# RaspberyConnector.net
KiCad netlist of a schematic drawn in Altium Designer
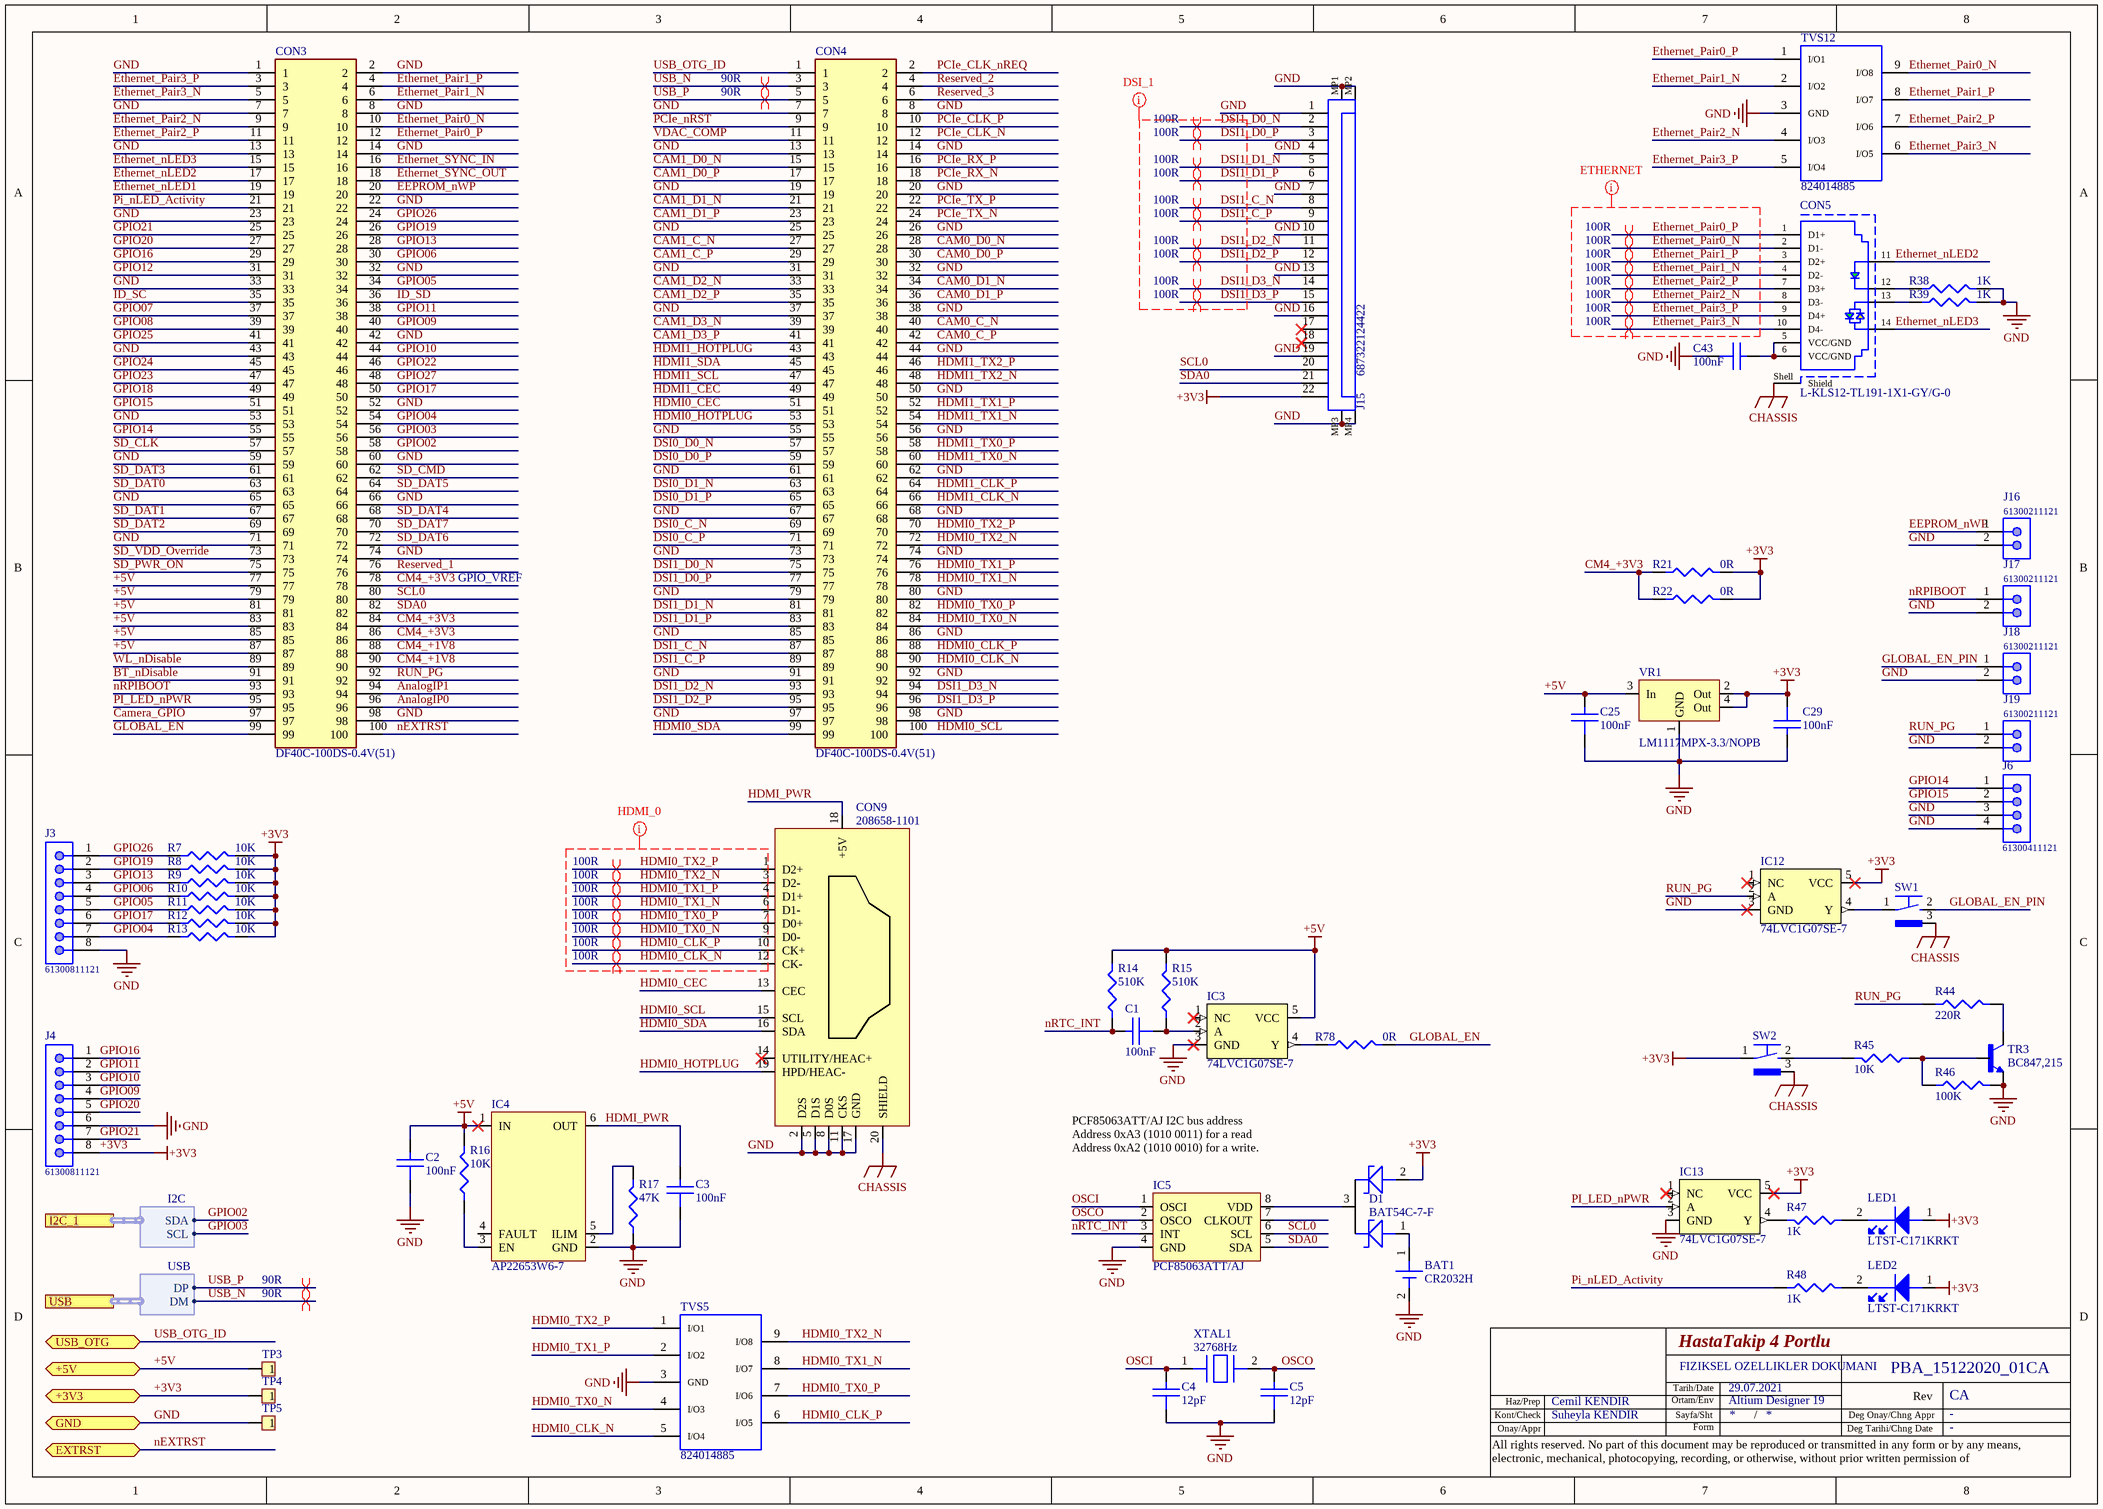
[diagram p0: RaspberyConnector.SchDoc]

(export (version "E")
  (design (tool "Eeschema 10.0.6"))
  (components
    (comp (ref "BAT1")
      (value "CR2032H")
      (footprint "CR2032H")
      (description "CR2032 Yatay Montaj")
      (libsource (lib "McmLibrary") (part "CR2032H"))
    )
    (comp (ref "C1")
      (value "100nF")
      (footprint "C0603")
      (description "100nF, 25V, X7R, 10%, 0603")
      (fields
        (field (name "MANUFACTURER") "Yageo")
        (field (name "MANUFACTURER PART NUMBER") "CC0603KRX7R8BB104")
      )
      (libsource (lib "McmLibrary") (part "CC0603KRX7R8BB104"))
    )
    (comp (ref "C2")
      (value "100nF")
      (footprint "C0603")
      (description "100nF, 25V, X7R, 10%, 0603")
      (fields
        (field (name "MANUFACTURER") "Yageo")
        (field (name "MANUFACTURER PART NUMBER") "CC0603KRX7R8BB104")
      )
      (libsource (lib "McmLibrary") (part "CC0603KRX7R8BB104"))
    )
    (comp (ref "C3")
      (value "100nF")
      (footprint "C0603")
      (description "100nF, 25V, X7R, 10%, 0603")
      (fields
        (field (name "MANUFACTURER") "Yageo")
        (field (name "MANUFACTURER PART NUMBER") "CC0603KRX7R8BB104")
      )
      (libsource (lib "McmLibrary") (part "CC0603KRX7R8BB104"))
    )
    (comp (ref "C4")
      (value "12pF")
      (footprint "C0603")
      (description "12pF 50V C0G 5% SMD 0603 125C T/R")
      (fields
        (field (name "MANUFACTURER") "Yageo")
        (field (name "MANUFACTURER PART NUMBER") "CC0603JRNPO9BN120")
      )
      (libsource (lib "McmLibrary") (part "CC0603JRNPO9BN120"))
    )
    (comp (ref "C5")
      (value "12pF")
      (footprint "C0603")
      (description "12pF 50V C0G 5% SMD 0603 125C T/R")
      (fields
        (field (name "MANUFACTURER") "Yageo")
        (field (name "MANUFACTURER PART NUMBER") "CC0603JRNPO9BN120")
      )
      (libsource (lib "McmLibrary") (part "CC0603JRNPO9BN120"))
    )
    (comp (ref "C25")
      (value "100nF")
      (footprint "C0603")
      (description "100nF, 25V, X7R, 10%, 0603")
      (fields
        (field (name "MANUFACTURER") "Yageo")
        (field (name "MANUFACTURER PART NUMBER") "CC0603KRX7R8BB104")
      )
      (libsource (lib "McmLibrary") (part "CC0603KRX7R8BB104"))
    )
    (comp (ref "C29")
      (value "100nF")
      (footprint "C0603")
      (description "100nF, 25V, X7R, 10%, 0603")
      (fields
        (field (name "MANUFACTURER") "Yageo")
        (field (name "MANUFACTURER PART NUMBER") "CC0603KRX7R8BB104")
      )
      (libsource (lib "McmLibrary") (part "CC0603KRX7R8BB104"))
    )
    (comp (ref "C43")
      (value "100nF")
      (footprint "C0603")
      (description "100nF, 25V, X7R, 10%, 0603")
      (fields
        (field (name "MANUFACTURER") "Yageo")
        (field (name "MANUFACTURER PART NUMBER") "CC0603KRX7R8BB104")
      )
      (libsource (lib "McmLibrary") (part "CC0603KRX7R8BB104"))
    )
    (comp (ref "CON3")
      (value "DF40C-100DS-0.4V(51)")
      (footprint "HRS_DF40C-100DS-0.4V(51)")
      (fields (field (name "MANUFACTURER") "Hirose"))
      (libsource (lib "McmLibrary") (part "DF40C-100DS-0.4V(51)"))
    )
    (comp (ref "CON4")
      (value "DF40C-100DS-0.4V(51)")
      (footprint "HRS_DF40C-100DS-0.4V(51)")
      (fields (field (name "MANUFACTURER") "Hirose"))
      (libsource (lib "McmLibrary") (part "DF40C-100DS-0.4V(51)"))
    )
    (comp (ref "CON5")
      (value "L-KLS12-TL191-1X1-GY/G-0")
      (footprint "L-KLS12-TL191-1X1-GY/G-0")
      (description "MODULAR JACK THT R/A 8P8C (RJ45,Ethernet) GRAY")
      (fields (field (name "MANUFACTURER") "KLS ELECTRONIC"))
      (libsource (lib "McmLibrary") (part "L-KLS12-TL191-1X1-GY/G-0"))
    )
    (comp (ref "CON9")
      (value "208658-1101")
      (footprint "2086581101")
      (description "HDMI; 0.5mm; v2.1; RT Angle; w/o Mylar; w/o Flange; 19 Circuits")
      (fields (field (name "MANUFACTURER") "Molex"))
      (libsource (lib "McmLibrary") (part "208658-1101"))
    )
    (comp (ref "D1")
      (value "BAT54C-7-F")
      (footprint "SOT23")
      (fields (field (name "MANUFACTURER") "Diodes"))
      (libsource (lib "McmLibrary") (part "BAT54C-7-F"))
    )
    (comp (ref "IC3")
      (value "74LVC1G07SE-7")
      (footprint "SOT353")
      (description "Buffer/Driver 1-CH Non-Inverting Open Drain CMOS 5-Pin SOT-353 T/R")
      (fields (field (name "MANUFACTURER") "Diodes"))
      (libsource (lib "InterfaceDriversReceiversTransceivers") (part "74LVC1G07SE-7"))
    )
    (comp (ref "IC4")
      (value "AP22653W6-7")
      (footprint "SOT23-6")
      (description "Power Switch/Driver 1:1 P-Channel 2.1A SOT-23-6")
      (fields (field (name "MANUFACTURER") "Diodes"))
      (libsource (lib "LoadDrivers") (part "AP22653W6-7"))
    )
    (comp (ref "IC5")
      (value "PCF85063ATT/AJ")
      (footprint "SOT505-1")
      (description "Real time clock, TSSOP-8,")
      (fields (field (name "MANUFACTURER") "NXP Semiconductors"))
      (libsource (lib "McmLibrary") (part "PCF85063ATT/AJ"))
    )
    (comp (ref "IC12")
      (value "74LVC1G07SE-7")
      (footprint "SOT353")
      (description "Buffer/Driver 1-CH Non-Inverting Open Drain CMOS 5-Pin SOT-353 T/R")
      (fields (field (name "MANUFACTURER") "Diodes"))
      (libsource (lib "InterfaceDriversReceiversTransceivers") (part "74LVC1G07SE-7"))
    )
    (comp (ref "IC13")
      (value "74LVC1G07SE-7")
      (footprint "SOT353")
      (description "Buffer/Driver 1-CH Non-Inverting Open Drain CMOS 5-Pin SOT-353 T/R")
      (fields (field (name "MANUFACTURER") "Diodes"))
      (libsource (lib "InterfaceDriversReceiversTransceivers") (part "74LVC1G07SE-7"))
    )
    (comp (ref "J3")
      (value "61300811121")
      (footprint "61300811121")
      (description "WR-PHD Pin Header, THT, pitch 2.54mm, Single Row, Vertical, 8pin")
      (fields (field (name "MANUFACTURER") "Wurth Electronics") (field (name "PUBLISHER") "Wurth Elektronik"))
      (libsource (lib "McmLibrary") (part "61300811121"))
    )
    (comp (ref "J4")
      (value "61300811121")
      (footprint "61300811121")
      (description "WR-PHD Pin Header, THT, pitch 2.54mm, Single Row, Vertical, 8pin")
      (fields (field (name "MANUFACTURER") "Wurth Electronics") (field (name "PUBLISHER") "Wurth Elektronik"))
      (libsource (lib "McmLibrary") (part "61300811121"))
    )
    (comp (ref "J6")
      (value "61300411121")
      (footprint "61300411121")
      (description "WR-PHD Pin Header, THT, pitch 2.54mm, Single Row, Vertical, 4pin")
      (fields (field (name "MANUFACTURER") "Wurth Electronics") (field (name "PUBLISHER") "Wurth Elektronik"))
      (libsource (lib "McmLibrary") (part "61300411121"))
    )
    (comp (ref "J15")
      (value "687322124422")
      (footprint "687322124422")
      (description "WR-FPC SMT ZIF Vertical, pitch 0.5mm, 22p")
      (fields (field (name "MANUFACTURER") "Wurth Elektronik") (field (name "PUBLISHER") "Wurth Elektronik"))
      (libsource (lib "Connectors") (part "687322124422"))
    )
    (comp (ref "J16")
      (value "61300211121")
      (footprint "61300211121")
      (description "WR-PHD Pin Header, THT, pitch 2.54mm, Single Row, Vertical, 2pin")
      (fields (field (name "MANUFACTURER") "Wurth Electronics") (field (name "PUBLISHER") "Wurth Elektronik"))
      (libsource (lib "McmLibrary") (part "61300211121"))
    )
    (comp (ref "J17")
      (value "61300211121")
      (footprint "61300211121")
      (description "WR-PHD Pin Header, THT, pitch 2.54mm, Single Row, Vertical, 2pin")
      (fields (field (name "MANUFACTURER") "Wurth Electronics") (field (name "PUBLISHER") "Wurth Elektronik"))
      (libsource (lib "McmLibrary") (part "61300211121"))
    )
    (comp (ref "J18")
      (value "61300211121")
      (footprint "61300211121")
      (description "WR-PHD Pin Header, THT, pitch 2.54mm, Single Row, Vertical, 2pin")
      (fields (field (name "MANUFACTURER") "Wurth Electronics") (field (name "PUBLISHER") "Wurth Elektronik"))
      (libsource (lib "McmLibrary") (part "61300211121"))
    )
    (comp (ref "J19")
      (value "61300211121")
      (footprint "61300211121")
      (description "WR-PHD Pin Header, THT, pitch 2.54mm, Single Row, Vertical, 2pin")
      (fields (field (name "MANUFACTURER") "Wurth Electronics") (field (name "PUBLISHER") "Wurth Elektronik"))
      (libsource (lib "McmLibrary") (part "61300211121"))
    )
    (comp (ref "LED1")
      (value "LTST-C171KRKT")
      (footprint "0805_RED")
      (description "LED RED CLEAR SMD")
      (fields (field (name "MANUFACTURER") "Vishay Lite-On"))
      (libsource (lib "McmLibrary") (part "LTST-C171KRKT"))
    )
    (comp (ref "LED2")
      (value "LTST-C171KRKT")
      (footprint "0805_RED")
      (description "LED RED CLEAR SMD")
      (fields (field (name "MANUFACTURER") "Vishay Lite-On"))
      (libsource (lib "McmLibrary") (part "LTST-C171KRKT"))
    )
    (comp (ref "R7")
      (value "10K")
      (footprint "R0603")
      (description "10K OHM 1% 1/10W 0603")
      (fields
        (field (name "MANUFACTURER") "Yageo")
        (field (name "MANUFACTURER PART NUMBER") "RT0603FRE0710KL")
      )
      (libsource (lib "McmLibrary") (part "RT0603FRE0710KL"))
    )
    (comp (ref "R8")
      (value "10K")
      (footprint "R0603")
      (description "10K OHM 1% 1/10W 0603")
      (fields
        (field (name "MANUFACTURER") "Yageo")
        (field (name "MANUFACTURER PART NUMBER") "RT0603FRE0710KL")
      )
      (libsource (lib "McmLibrary") (part "RT0603FRE0710KL"))
    )
    (comp (ref "R9")
      (value "10K")
      (footprint "R0603")
      (description "10K OHM 1% 1/10W 0603")
      (fields
        (field (name "MANUFACTURER") "Yageo")
        (field (name "MANUFACTURER PART NUMBER") "RT0603FRE0710KL")
      )
      (libsource (lib "McmLibrary") (part "RT0603FRE0710KL"))
    )
    (comp (ref "R10")
      (value "10K")
      (footprint "R0603")
      (description "10K OHM 1% 1/10W 0603")
      (fields
        (field (name "MANUFACTURER") "Yageo")
        (field (name "MANUFACTURER PART NUMBER") "RT0603FRE0710KL")
      )
      (libsource (lib "McmLibrary") (part "RT0603FRE0710KL"))
    )
    (comp (ref "R11")
      (value "10K")
      (footprint "R0603")
      (description "10K OHM 1% 1/10W 0603")
      (fields
        (field (name "MANUFACTURER") "Yageo")
        (field (name "MANUFACTURER PART NUMBER") "RT0603FRE0710KL")
      )
      (libsource (lib "McmLibrary") (part "RT0603FRE0710KL"))
    )
    (comp (ref "R12")
      (value "10K")
      (footprint "R0603")
      (description "10K OHM 1% 1/10W 0603")
      (fields
        (field (name "MANUFACTURER") "Yageo")
        (field (name "MANUFACTURER PART NUMBER") "RT0603FRE0710KL")
      )
      (libsource (lib "McmLibrary") (part "RT0603FRE0710KL"))
    )
    (comp (ref "R13")
      (value "10K")
      (footprint "R0603")
      (description "10K OHM 1% 1/10W 0603")
      (fields
        (field (name "MANUFACTURER") "Yageo")
        (field (name "MANUFACTURER PART NUMBER") "RT0603FRE0710KL")
      )
      (libsource (lib "McmLibrary") (part "RT0603FRE0710KL"))
    )
    (comp (ref "R14")
      (value "510K")
      (footprint "R0603")
      (description "510K, 1%, 1/10W, 0603")
      (fields
        (field (name "MANUFACTURER") "Yageo")
        (field (name "MANUFACTURER PART NUMBER") "RC0603FR-07510KL")
      )
      (libsource (lib "McmLibrary") (part "RC0603FR-07510KL"))
    )
    (comp (ref "R15")
      (value "510K")
      (footprint "R0603")
      (description "510K, 1%, 1/10W, 0603")
      (fields
        (field (name "MANUFACTURER") "Yageo")
        (field (name "MANUFACTURER PART NUMBER") "RC0603FR-07510KL")
      )
      (libsource (lib "McmLibrary") (part "RC0603FR-07510KL"))
    )
    (comp (ref "R16")
      (value "10K")
      (footprint "R0603")
      (description "10K OHM 1% 1/10W 0603")
      (fields
        (field (name "MANUFACTURER") "Yageo")
        (field (name "MANUFACTURER PART NUMBER") "RT0603FRE0710KL")
      )
      (libsource (lib "McmLibrary") (part "RT0603FRE0710KL"))
    )
    (comp (ref "R17")
      (value "47K")
      (footprint "R0603")
      (description "47K, 50V, 1/10W, 1%, 0603")
      (fields
        (field (name "MANUFACTURER") "Yageo")
        (field (name "MANUFACTURER PART NUMBER") "RC0603FR-0747KL")
      )
      (libsource (lib "McmLibrary") (part "RC0603FR-0747KL"))
    )
    (comp (ref "R21")
      (value "0R")
      (footprint "R0603")
      (description "0R ,%1 ,1/10 W ,0603")
      (fields
        (field (name "MANUFACTURER") "Yageo")
        (field (name "MANUFACTURER PART NUMBER") "RC0603FR-070RL")
      )
      (libsource (lib "McmLibrary") (part "RC0603FR-070RL"))
    )
    (comp (ref "R22")
      (value "0R")
      (footprint "R0603")
      (description "0R ,%1 ,1/10 W ,0603")
      (fields
        (field (name "MANUFACTURER") "Yageo")
        (field (name "MANUFACTURER PART NUMBER") "RC0603FR-070RL")
      )
      (libsource (lib "McmLibrary") (part "RC0603FR-070RL"))
    )
    (comp (ref "R38")
      (value "1K")
      (footprint "R0603")
      (description "1K ,%1 ,1/10 W ,0603")
      (fields
        (field (name "MANUFACTURER") "Yageo")
        (field (name "MANUFACTURER PART NUMBER") "RC0603FR-071KL")
      )
      (libsource (lib "McmLibrary") (part "RC0603FR-071KL"))
    )
    (comp (ref "R39")
      (value "1K")
      (footprint "R0603")
      (description "1K ,%1 ,1/10 W ,0603")
      (fields
        (field (name "MANUFACTURER") "Yageo")
        (field (name "MANUFACTURER PART NUMBER") "RC0603FR-071KL")
      )
      (libsource (lib "McmLibrary") (part "RC0603FR-071KL"))
    )
    (comp (ref "R44")
      (value "220R")
      (footprint "R0603")
      (description "220 R, %1, 1/10W, 0603")
      (fields
        (field (name "MANUFACTURER") "Yageo")
        (field (name "MANUFACTURER PART NUMBER") "RC0603FR-07220RL")
      )
      (libsource (lib "McmLibrary") (part "RC0603FR-07220RL"))
    )
    (comp (ref "R45")
      (value "10K")
      (footprint "R0603")
      (description "10K OHM 1% 1/10W 0603")
      (fields
        (field (name "MANUFACTURER") "Yageo")
        (field (name "MANUFACTURER PART NUMBER") "RT0603FRE0710KL")
      )
      (libsource (lib "McmLibrary") (part "RT0603FRE0710KL"))
    )
    (comp (ref "R46")
      (value "100K")
      (footprint "R0603")
      (description "100K ,%1 ,1/10 W ,0603")
      (fields
        (field (name "MANUFACTURER") "Yageo")
        (field (name "MANUFACTURER PART NUMBER") "RC0603FR-07100KL")
      )
      (libsource (lib "McmLibrary") (part "RC0603FR-07100KL"))
    )
    (comp (ref "R47")
      (value "1K")
      (footprint "R0603")
      (description "1K ,%1 ,1/10 W ,0603")
      (fields
        (field (name "MANUFACTURER") "Yageo")
        (field (name "MANUFACTURER PART NUMBER") "RC0603FR-071KL")
      )
      (libsource (lib "McmLibrary") (part "RC0603FR-071KL"))
    )
    (comp (ref "R48")
      (value "1K")
      (footprint "R0603")
      (description "1K ,%1 ,1/10 W ,0603")
      (fields
        (field (name "MANUFACTURER") "Yageo")
        (field (name "MANUFACTURER PART NUMBER") "RC0603FR-071KL")
      )
      (libsource (lib "McmLibrary") (part "RC0603FR-071KL"))
    )
    (comp (ref "R78")
      (value "0R")
      (footprint "R0603")
      (description "0R ,%1 ,1/10 W ,0603")
      (fields
        (field (name "MANUFACTURER") "Yageo")
        (field (name "MANUFACTURER PART NUMBER") "RC0603FR-070RL")
      )
      (libsource (lib "McmLibrary") (part "RC0603FR-070RL"))
    )
    (comp (ref "SW1")
      (value "FSMRACDAH")
      (footprint "FSMRACDAH")
      (description "Tactile Switches 6MM HGH TMP W/SQ ACT R/A TACT SWITCH")
      (fields (field (name "MANUFACTURER") "TE Connectivity"))
      (libsource (lib "McmLibrary") (part "FSMRACDAH"))
    )
    (comp (ref "SW2")
      (value "FSMRACDAH")
      (footprint "FSMRACDAH")
      (description "Tactile Switches 6MM HGH TMP W/SQ ACT R/A TACT SWITCH")
      (fields (field (name "MANUFACTURER") "TE Connectivity"))
      (libsource (lib "McmLibrary") (part "FSMRACDAH"))
    )
    (comp (ref "TP3")
      (value "TestPoint1")
      (footprint "SMD_2mmPoint")
      (description "test ölçüm noktası")
      (libsource (lib "McmLibrary") (part "TestPoint1"))
    )
    (comp (ref "TP4")
      (value "TestPoint1")
      (footprint "SMD_2mmPoint")
      (description "test ölçüm noktası")
      (libsource (lib "McmLibrary") (part "TestPoint1"))
    )
    (comp (ref "TP5")
      (value "TestPoint1")
      (footprint "SMD_2mmPoint")
      (description "test ölçüm noktası")
      (libsource (lib "McmLibrary") (part "TestPoint1"))
    )
    (comp (ref "TR3")
      (value "BC847,215")
      (footprint "SOT23")
      (description "TRANS NPN 45V 0.1A SOT23")
      (fields (field (name "MANUFACTURER") "Nexperia"))
      (libsource (lib "McmLibrary") (part "BC847,215"))
    )
    (comp (ref "TVS5")
      (value "824014885")
      (footprint "WE-TVS_DFN3810-9L")
      (description "TVS DIODE 5V 10.5V DFN3810-9")
      (fields (field (name "MANUFACTURER") "Wurth Electronics"))
      (libsource (lib "TVS") (part "824014885"))
    )
    (comp (ref "TVS12")
      (value "824014885")
      (footprint "WE-TVS_DFN3810-9L")
      (description "TVS DIODE 5V 10.5V DFN3810-9")
      (fields (field (name "MANUFACTURER") "Wurth Electronics"))
      (libsource (lib "TVS") (part "824014885"))
    )
    (comp (ref "VR1")
      (value "LM1117MPX-3.3/NOPB")
      (footprint "SOT223-3")
      (description "TEXAS INSTRUMENTS   LM1117MPX-3.3/NOPB.   LINEAR REG, FIX, 3.3V, 800MA, SOT-223-4, FULL REEL")
      (fields (field (name "MANUFACTURER") "Texas Instruments"))
      (libsource (lib "Regulator") (part "LM1117MPX-3.3/NOPB"))
    )
    (comp (ref "XTAL1")
      (value "32768Hz")
      (footprint "ForkCrystal")
      (description "CRYSTAL 32.7680KHZ 12.5PF T/H")
      (fields
        (field (name "MANUFACTURER") "Abracon")
        (field (name "MANUFACTURER PART NUMBER") "AB26T-32.768KHZ")
      )
      (libsource (lib "McmLibrary") (part "AB26T-32.768KHZ"))
    )
  )
  (nets
    (net (code "3") (name "+3V3") (class "Default")
      (node (ref "C29") (pin "2") (pintype "passive"))
      (node (ref "D1") (pin "2") (pinfunction "K_2") (pintype "passive"))
      (node (ref "IC12") (pin "5") (pinfunction "VCC_5") (pintype "power_in"))
      (node (ref "IC13") (pin "5") (pinfunction "VCC_5") (pintype "power_in"))
      (node (ref "J15") (pin "22") (pinfunction "22_22") (pintype "passive"))
      (node (ref "J4") (pin "8") (pinfunction "8_8") (pintype "passive"))
      (node (ref "LED1") (pin "1") (pinfunction "1_1") (pintype "passive"))
      (node (ref "LED2") (pin "1") (pinfunction "1_1") (pintype "passive"))
      (node (ref "R10") (pin "2") (pinfunction "2_2") (pintype "passive"))
      (node (ref "R11") (pin "2") (pinfunction "2_2") (pintype "passive"))
      (node (ref "R12") (pin "2") (pinfunction "2_2") (pintype "passive"))
      (node (ref "R13") (pin "2") (pinfunction "2_2") (pintype "passive"))
      (node (ref "R21") (pin "2") (pinfunction "2_2") (pintype "passive"))
      (node (ref "R22") (pin "2") (pinfunction "2_2") (pintype "passive"))
      (node (ref "R7") (pin "2") (pinfunction "2_2") (pintype "passive"))
      (node (ref "R8") (pin "2") (pinfunction "2_2") (pintype "passive"))
      (node (ref "R9") (pin "2") (pinfunction "2_2") (pintype "passive"))
      (node (ref "SW2") (pin "1") (pinfunction "1_1") (pintype "passive"))
      (node (ref "TP4") (pin "1") (pinfunction "1_1") (pintype "passive"))
      (node (ref "VR1") (pin "2") (pinfunction "Out_2") (pintype "passive"))
      (node (ref "VR1") (pin "4") (pinfunction "Out_4") (pintype "passive"))
    )
    (net (code "4") (name "+5V") (class "Default")
      (node (ref "C2") (pin "1") (pintype "passive"))
      (node (ref "C25") (pin "1") (pintype "passive"))
      (node (ref "CON3") (pin "77") (pinfunction "77_77") (pintype "passive"))
      (node (ref "CON3") (pin "79") (pinfunction "79_79") (pintype "passive"))
      (node (ref "CON3") (pin "81") (pinfunction "81_81") (pintype "passive"))
      (node (ref "CON3") (pin "83") (pinfunction "83_83") (pintype "passive"))
      (node (ref "CON3") (pin "85") (pinfunction "85_85") (pintype "passive"))
      (node (ref "CON3") (pin "87") (pinfunction "87_87") (pintype "passive"))
      (node (ref "IC3") (pin "5") (pinfunction "VCC_5") (pintype "power_in"))
      (node (ref "IC4") (pin "1") (pinfunction "IN_1") (pintype "passive"))
      (node (ref "R14") (pin "2") (pinfunction "2_2") (pintype "passive"))
      (node (ref "R15") (pin "2") (pinfunction "2_2") (pintype "passive"))
      (node (ref "R16") (pin "2") (pinfunction "2_2") (pintype "passive"))
      (node (ref "TP3") (pin "1") (pinfunction "1_1") (pintype "passive"))
      (node (ref "VR1") (pin "3") (pinfunction "In_3") (pintype "passive"))
    )
    (net (code "5") (name "/AnalogIP0") (class "Default")
      (node (ref "CON3") (pin "96") (pinfunction "96_96") (pintype "passive"))
    )
    (net (code "6") (name "/AnalogIP1") (class "Default")
      (node (ref "CON3") (pin "94") (pinfunction "94_94") (pintype "passive"))
    )
    (net (code "7") (name "/BT_nDisable") (class "Default")
      (node (ref "CON3") (pin "91") (pinfunction "91_91") (pintype "passive"))
    )
    (net (code "8") (name "/CAM0_C_N") (class "Default")
      (node (ref "CON4") (pin "40") (pinfunction "40_40") (pintype "passive"))
    )
    (net (code "9") (name "/CAM0_C_P") (class "Default")
      (node (ref "CON4") (pin "42") (pinfunction "42_42") (pintype "passive"))
    )
    (net (code "10") (name "/CAM0_D0_N") (class "Default")
      (node (ref "CON4") (pin "28") (pinfunction "28_28") (pintype "passive"))
    )
    (net (code "11") (name "/CAM0_D0_P") (class "Default")
      (node (ref "CON4") (pin "30") (pinfunction "30_30") (pintype "passive"))
    )
    (net (code "12") (name "/CAM0_D1_N") (class "Default")
      (node (ref "CON4") (pin "34") (pinfunction "34_34") (pintype "passive"))
    )
    (net (code "13") (name "/CAM0_D1_P") (class "Default")
      (node (ref "CON4") (pin "36") (pinfunction "36_36") (pintype "passive"))
    )
    (net (code "14") (name "/CAM1_C_N") (class "Default")
      (node (ref "CON4") (pin "27") (pinfunction "27_27") (pintype "passive"))
    )
    (net (code "15") (name "/CAM1_C_P") (class "Default")
      (node (ref "CON4") (pin "29") (pinfunction "29_29") (pintype "passive"))
    )
    (net (code "16") (name "/CAM1_D0_N") (class "Default")
      (node (ref "CON4") (pin "15") (pinfunction "15_15") (pintype "passive"))
    )
    (net (code "17") (name "/CAM1_D0_P") (class "Default")
      (node (ref "CON4") (pin "17") (pinfunction "17_17") (pintype "passive"))
    )
    (net (code "18") (name "/CAM1_D1_N") (class "Default")
      (node (ref "CON4") (pin "21") (pinfunction "21_21") (pintype "passive"))
    )
    (net (code "19") (name "/CAM1_D1_P") (class "Default")
      (node (ref "CON4") (pin "23") (pinfunction "23_23") (pintype "passive"))
    )
    (net (code "20") (name "/CAM1_D2_N") (class "Default")
      (node (ref "CON4") (pin "33") (pinfunction "33_33") (pintype "passive"))
    )
    (net (code "21") (name "/CAM1_D2_P") (class "Default")
      (node (ref "CON4") (pin "35") (pinfunction "35_35") (pintype "passive"))
    )
    (net (code "22") (name "/CAM1_D3_N") (class "Default")
      (node (ref "CON4") (pin "39") (pinfunction "39_39") (pintype "passive"))
    )
    (net (code "23") (name "/CAM1_D3_P") (class "Default")
      (node (ref "CON4") (pin "41") (pinfunction "41_41") (pintype "passive"))
    )
    (net (code "24") (name "/CM4_+1V8") (class "Default")
      (node (ref "CON3") (pin "88") (pinfunction "88_88") (pintype "passive"))
      (node (ref "CON3") (pin "90") (pinfunction "90_90") (pintype "passive"))
    )
    (net (code "25") (name "/CM4_+3V3") (class "Default")
      (node (ref "CON3") (pin "78") (pinfunction "78_78") (pintype "passive"))
      (node (ref "CON3") (pin "84") (pinfunction "84_84") (pintype "passive"))
      (node (ref "CON3") (pin "86") (pinfunction "86_86") (pintype "passive"))
      (node (ref "R21") (pin "1") (pinfunction "1_1") (pintype "passive"))
      (node (ref "R22") (pin "1") (pinfunction "1_1") (pintype "passive"))
    )
    (net (code "26") (name "/Camera_GPIO") (class "Default")
      (node (ref "CON3") (pin "97") (pinfunction "97_97") (pintype "passive"))
    )
    (net (code "27") (name "/DSI0_C_N") (class "Default")
      (node (ref "CON4") (pin "69") (pinfunction "69_69") (pintype "passive"))
    )
    (net (code "28") (name "/DSI0_C_P") (class "Default")
      (node (ref "CON4") (pin "71") (pinfunction "71_71") (pintype "passive"))
    )
    (net (code "29") (name "/DSI0_D0_N") (class "Default")
      (node (ref "CON4") (pin "57") (pinfunction "57_57") (pintype "passive"))
    )
    (net (code "30") (name "/DSI0_D0_P") (class "Default")
      (node (ref "CON4") (pin "59") (pinfunction "59_59") (pintype "passive"))
    )
    (net (code "31") (name "/DSI0_D1_N") (class "Default")
      (node (ref "CON4") (pin "63") (pinfunction "63_63") (pintype "passive"))
    )
    (net (code "32") (name "/DSI0_D1_P") (class "Default")
      (node (ref "CON4") (pin "65") (pinfunction "65_65") (pintype "passive"))
    )
    (net (code "33") (name "/DSI1_C_N") (class "Default")
      (node (ref "CON4") (pin "87") (pinfunction "87_87") (pintype "passive"))
      (node (ref "J15") (pin "8") (pinfunction "8_8") (pintype "passive"))
    )
    (net (code "34") (name "/DSI1_C_P") (class "Default")
      (node (ref "CON4") (pin "89") (pinfunction "89_89") (pintype "passive"))
      (node (ref "J15") (pin "9") (pinfunction "9_9") (pintype "passive"))
    )
    (net (code "35") (name "/DSI1_D0_N") (class "Default")
      (node (ref "CON4") (pin "75") (pinfunction "75_75") (pintype "passive"))
      (node (ref "J15") (pin "2") (pinfunction "2_2") (pintype "passive"))
    )
    (net (code "36") (name "/DSI1_D0_P") (class "Default")
      (node (ref "CON4") (pin "77") (pinfunction "77_77") (pintype "passive"))
      (node (ref "J15") (pin "3") (pinfunction "3_3") (pintype "passive"))
    )
    (net (code "37") (name "/DSI1_D1_N") (class "Default")
      (node (ref "CON4") (pin "81") (pinfunction "81_81") (pintype "passive"))
      (node (ref "J15") (pin "5") (pinfunction "5_5") (pintype "passive"))
    )
    (net (code "38") (name "/DSI1_D1_P") (class "Default")
      (node (ref "CON4") (pin "83") (pinfunction "83_83") (pintype "passive"))
      (node (ref "J15") (pin "6") (pinfunction "6_6") (pintype "passive"))
    )
    (net (code "39") (name "/DSI1_D2_N") (class "Default")
      (node (ref "CON4") (pin "93") (pinfunction "93_93") (pintype "passive"))
      (node (ref "J15") (pin "11") (pinfunction "11_11") (pintype "passive"))
    )
    (net (code "40") (name "/DSI1_D2_P") (class "Default")
      (node (ref "CON4") (pin "95") (pinfunction "95_95") (pintype "passive"))
      (node (ref "J15") (pin "12") (pinfunction "12_12") (pintype "passive"))
    )
    (net (code "41") (name "/DSI1_D3_N") (class "Default")
      (node (ref "CON4") (pin "94") (pinfunction "94_94") (pintype "passive"))
      (node (ref "J15") (pin "14") (pinfunction "14_14") (pintype "passive"))
    )
    (net (code "42") (name "/DSI1_D3_P") (class "Default")
      (node (ref "CON4") (pin "96") (pinfunction "96_96") (pintype "passive"))
      (node (ref "J15") (pin "15") (pinfunction "15_15") (pintype "passive"))
    )
    (net (code "43") (name "/EEPROM_nWP") (class "Default")
      (node (ref "CON3") (pin "20") (pinfunction "20_20") (pintype "passive"))
      (node (ref "J16") (pin "1") (pinfunction "1_1") (pintype "passive"))
    )
    (net (code "44") (name "/Ethernet_Pair0_N") (class "Default")
      (node (ref "CON3") (pin "10") (pinfunction "10_10") (pintype "passive"))
      (node (ref "CON5") (pin "2") (pinfunction "D1-_2") (pintype "passive"))
      (node (ref "TVS12") (pin "9") (pinfunction "I/O8_9") (pintype "passive"))
    )
    (net (code "45") (name "/Ethernet_Pair0_P") (class "Default")
      (node (ref "CON3") (pin "12") (pinfunction "12_12") (pintype "passive"))
      (node (ref "CON5") (pin "1") (pinfunction "D1+_1") (pintype "passive"))
      (node (ref "TVS12") (pin "1") (pinfunction "I/O1_1") (pintype "passive"))
    )
    (net (code "46") (name "/Ethernet_Pair1_N") (class "Default")
      (node (ref "CON3") (pin "6") (pinfunction "6_6") (pintype "passive"))
      (node (ref "CON5") (pin "4") (pinfunction "D2-_4") (pintype "passive"))
      (node (ref "TVS12") (pin "2") (pinfunction "I/O2_2") (pintype "passive"))
    )
    (net (code "47") (name "/Ethernet_Pair1_P") (class "Default")
      (node (ref "CON3") (pin "4") (pinfunction "4_4") (pintype "passive"))
      (node (ref "CON5") (pin "3") (pinfunction "D2+_3") (pintype "passive"))
      (node (ref "TVS12") (pin "8") (pinfunction "I/O7_8") (pintype "passive"))
    )
    (net (code "48") (name "/Ethernet_Pair2_N") (class "Default")
      (node (ref "CON3") (pin "9") (pinfunction "9_9") (pintype "passive"))
      (node (ref "CON5") (pin "8") (pinfunction "D3-_8") (pintype "passive"))
      (node (ref "TVS12") (pin "4") (pinfunction "I/O3_4") (pintype "passive"))
    )
    (net (code "49") (name "/Ethernet_Pair2_P") (class "Default")
      (node (ref "CON3") (pin "11") (pinfunction "11_11") (pintype "passive"))
      (node (ref "CON5") (pin "7") (pinfunction "D3+_7") (pintype "passive"))
      (node (ref "TVS12") (pin "7") (pinfunction "I/O6_7") (pintype "passive"))
    )
    (net (code "50") (name "/Ethernet_Pair3_N") (class "Default")
      (node (ref "CON3") (pin "5") (pinfunction "5_5") (pintype "passive"))
      (node (ref "CON5") (pin "10") (pinfunction "D4-_10") (pintype "passive"))
      (node (ref "TVS12") (pin "6") (pinfunction "I/O5_6") (pintype "passive"))
    )
    (net (code "51") (name "/Ethernet_Pair3_P") (class "Default")
      (node (ref "CON3") (pin "3") (pinfunction "3_3") (pintype "passive"))
      (node (ref "CON5") (pin "9") (pinfunction "D4+_9") (pintype "passive"))
      (node (ref "TVS12") (pin "5") (pinfunction "I/O4_5") (pintype "passive"))
    )
    (net (code "52") (name "/Ethernet_SYNC_IN") (class "Default")
      (node (ref "CON3") (pin "16") (pinfunction "16_16") (pintype "passive"))
    )
    (net (code "53") (name "/Ethernet_SYNC_OUT") (class "Default")
      (node (ref "CON3") (pin "18") (pinfunction "18_18") (pintype "passive"))
    )
    (net (code "54") (name "/Ethernet_nLED1") (class "Default")
      (node (ref "CON3") (pin "19") (pinfunction "19_19") (pintype "passive"))
    )
    (net (code "55") (name "/Ethernet_nLED2") (class "Default")
      (node (ref "CON3") (pin "17") (pinfunction "17_17") (pintype "passive"))
      (node (ref "CON5") (pin "11") (pinfunction "11_11") (pintype "passive"))
    )
    (net (code "56") (name "/Ethernet_nLED3") (class "Default")
      (node (ref "CON3") (pin "15") (pinfunction "15_15") (pintype "passive"))
      (node (ref "CON5") (pin "14") (pinfunction "14_14") (pintype "passive"))
    )
    (net (code "57") (name "/GLOBAL_EN") (class "Default")
      (node (ref "CON3") (pin "99") (pinfunction "99_99") (pintype "passive"))
      (node (ref "R78") (pin "2") (pinfunction "2_2") (pintype "passive"))
    )
    (net (code "58") (name "/GLOBAL_EN_PIN") (class "Default")
      (node (ref "J18") (pin "1") (pinfunction "1_1") (pintype "passive"))
      (node (ref "SW1") (pin "2") (pinfunction "2_2") (pintype "passive"))
    )
    (net (code "59") (name "/GPIO02") (class "Default")
      (node (ref "CON3") (pin "58") (pinfunction "58_58") (pintype "passive"))
    )
    (net (code "60") (name "/GPIO03") (class "Default")
      (node (ref "CON3") (pin "56") (pinfunction "56_56") (pintype "passive"))
    )
    (net (code "61") (name "/GPIO04") (class "Default")
      (node (ref "CON3") (pin "54") (pinfunction "54_54") (pintype "passive"))
      (node (ref "J3") (pin "7") (pinfunction "7_7") (pintype "passive"))
      (node (ref "R13") (pin "1") (pinfunction "1_1") (pintype "passive"))
    )
    (net (code "62") (name "/GPIO05") (class "Default")
      (node (ref "CON3") (pin "34") (pinfunction "34_34") (pintype "passive"))
      (node (ref "J3") (pin "5") (pinfunction "5_5") (pintype "passive"))
      (node (ref "R11") (pin "1") (pinfunction "1_1") (pintype "passive"))
    )
    (net (code "63") (name "/GPIO06") (class "Default")
      (node (ref "CON3") (pin "30") (pinfunction "30_30") (pintype "passive"))
      (node (ref "J3") (pin "4") (pinfunction "4_4") (pintype "passive"))
      (node (ref "R10") (pin "1") (pinfunction "1_1") (pintype "passive"))
    )
    (net (code "64") (name "/GPIO07") (class "Default")
      (node (ref "CON3") (pin "37") (pinfunction "37_37") (pintype "passive"))
    )
    (net (code "65") (name "/GPIO08") (class "Default")
      (node (ref "CON3") (pin "39") (pinfunction "39_39") (pintype "passive"))
    )
    (net (code "66") (name "/GPIO09") (class "Default")
      (node (ref "CON3") (pin "40") (pinfunction "40_40") (pintype "passive"))
      (node (ref "J4") (pin "4") (pinfunction "4_4") (pintype "passive"))
    )
    (net (code "67") (name "/GPIO10") (class "Default")
      (node (ref "CON3") (pin "44") (pinfunction "44_44") (pintype "passive"))
      (node (ref "J4") (pin "3") (pinfunction "3_3") (pintype "passive"))
    )
    (net (code "68") (name "/GPIO11") (class "Default")
      (node (ref "CON3") (pin "38") (pinfunction "38_38") (pintype "passive"))
      (node (ref "J4") (pin "2") (pinfunction "2_2") (pintype "passive"))
    )
    (net (code "69") (name "/GPIO12") (class "Default")
      (node (ref "CON3") (pin "31") (pinfunction "31_31") (pintype "passive"))
    )
    (net (code "70") (name "/GPIO13") (class "Default")
      (node (ref "CON3") (pin "28") (pinfunction "28_28") (pintype "passive"))
      (node (ref "J3") (pin "3") (pinfunction "3_3") (pintype "passive"))
      (node (ref "R9") (pin "1") (pinfunction "1_1") (pintype "passive"))
    )
    (net (code "71") (name "/GPIO14") (class "Default")
      (node (ref "CON3") (pin "55") (pinfunction "55_55") (pintype "passive"))
      (node (ref "J6") (pin "1") (pinfunction "1_1") (pintype "passive"))
    )
    (net (code "72") (name "/GPIO15") (class "Default")
      (node (ref "CON3") (pin "51") (pinfunction "51_51") (pintype "passive"))
      (node (ref "J6") (pin "2") (pinfunction "2_2") (pintype "passive"))
    )
    (net (code "73") (name "/GPIO16") (class "Default")
      (node (ref "CON3") (pin "29") (pinfunction "29_29") (pintype "passive"))
      (node (ref "J4") (pin "1") (pinfunction "1_1") (pintype "passive"))
    )
    (net (code "74") (name "/GPIO17") (class "Default")
      (node (ref "CON3") (pin "50") (pinfunction "50_50") (pintype "passive"))
      (node (ref "J3") (pin "6") (pinfunction "6_6") (pintype "passive"))
      (node (ref "R12") (pin "1") (pinfunction "1_1") (pintype "passive"))
    )
    (net (code "75") (name "/GPIO18") (class "Default")
      (node (ref "CON3") (pin "49") (pinfunction "49_49") (pintype "passive"))
    )
    (net (code "76") (name "/GPIO19") (class "Default")
      (node (ref "CON3") (pin "26") (pinfunction "26_26") (pintype "passive"))
      (node (ref "J3") (pin "2") (pinfunction "2_2") (pintype "passive"))
      (node (ref "R8") (pin "1") (pinfunction "1_1") (pintype "passive"))
    )
    (net (code "77") (name "/GPIO20") (class "Default")
      (node (ref "CON3") (pin "27") (pinfunction "27_27") (pintype "passive"))
      (node (ref "J4") (pin "5") (pinfunction "5_5") (pintype "passive"))
    )
    (net (code "78") (name "/GPIO21") (class "Default")
      (node (ref "CON3") (pin "25") (pinfunction "25_25") (pintype "passive"))
      (node (ref "J4") (pin "7") (pinfunction "7_7") (pintype "passive"))
    )
    (net (code "79") (name "/GPIO22") (class "Default")
      (node (ref "CON3") (pin "46") (pinfunction "46_46") (pintype "passive"))
    )
    (net (code "80") (name "/GPIO23") (class "Default")
      (node (ref "CON3") (pin "47") (pinfunction "47_47") (pintype "passive"))
    )
    (net (code "81") (name "/GPIO24") (class "Default")
      (node (ref "CON3") (pin "45") (pinfunction "45_45") (pintype "passive"))
    )
    (net (code "82") (name "/GPIO25") (class "Default")
      (node (ref "CON3") (pin "41") (pinfunction "41_41") (pintype "passive"))
    )
    (net (code "83") (name "/GPIO26") (class "Default")
      (node (ref "CON3") (pin "24") (pinfunction "24_24") (pintype "passive"))
      (node (ref "J3") (pin "1") (pinfunction "1_1") (pintype "passive"))
      (node (ref "R7") (pin "1") (pinfunction "1_1") (pintype "passive"))
    )
    (net (code "84") (name "/GPIO27") (class "Default")
      (node (ref "CON3") (pin "48") (pinfunction "48_48") (pintype "passive"))
    )
    (net (code "85") (name "/HDMI0_CEC") (class "Default")
      (node (ref "CON4") (pin "51") (pinfunction "51_51") (pintype "passive"))
      (node (ref "CON9") (pin "13") (pinfunction "CEC_13") (pintype "passive"))
    )
    (net (code "86") (name "/HDMI0_CLK_N") (class "Default")
      (node (ref "CON4") (pin "90") (pinfunction "90_90") (pintype "passive"))
      (node (ref "CON9") (pin "12") (pinfunction "CK-_12") (pintype "passive"))
      (node (ref "TVS5") (pin "5") (pinfunction "I/O4_5") (pintype "passive"))
    )
    (net (code "87") (name "/HDMI0_CLK_P") (class "Default")
      (node (ref "CON4") (pin "88") (pinfunction "88_88") (pintype "passive"))
      (node (ref "CON9") (pin "10") (pinfunction "CK+_10") (pintype "passive"))
      (node (ref "TVS5") (pin "6") (pinfunction "I/O5_6") (pintype "passive"))
    )
    (net (code "88") (name "/HDMI0_HOTPLUG") (class "Default")
      (node (ref "CON4") (pin "53") (pinfunction "53_53") (pintype "passive"))
      (node (ref "CON9") (pin "19") (pinfunction "HPD/HEAC-_19") (pintype "passive"))
    )
    (net (code "89") (name "/HDMI0_SCL") (class "Default")
      (node (ref "CON4") (pin "100") (pinfunction "100_100") (pintype "passive"))
      (node (ref "CON9") (pin "15") (pinfunction "SCL_15") (pintype "passive"))
    )
    (net (code "90") (name "/HDMI0_SDA") (class "Default")
      (node (ref "CON4") (pin "99") (pinfunction "99_99") (pintype "passive"))
      (node (ref "CON9") (pin "16") (pinfunction "SDA_16") (pintype "passive"))
    )
    (net (code "91") (name "/HDMI0_TX0_N") (class "Default")
      (node (ref "CON4") (pin "84") (pinfunction "84_84") (pintype "passive"))
      (node (ref "CON9") (pin "9") (pinfunction "D0-_9") (pintype "passive"))
      (node (ref "TVS5") (pin "4") (pinfunction "I/O3_4") (pintype "passive"))
    )
    (net (code "92") (name "/HDMI0_TX0_P") (class "Default")
      (node (ref "CON4") (pin "82") (pinfunction "82_82") (pintype "passive"))
      (node (ref "CON9") (pin "7") (pinfunction "D0+_7") (pintype "passive"))
      (node (ref "TVS5") (pin "7") (pinfunction "I/O6_7") (pintype "passive"))
    )
    (net (code "93") (name "/HDMI0_TX1_N") (class "Default")
      (node (ref "CON4") (pin "78") (pinfunction "78_78") (pintype "passive"))
      (node (ref "CON9") (pin "6") (pinfunction "D1-_6") (pintype "passive"))
      (node (ref "TVS5") (pin "8") (pinfunction "I/O7_8") (pintype "passive"))
    )
    (net (code "94") (name "/HDMI0_TX1_P") (class "Default")
      (node (ref "CON4") (pin "76") (pinfunction "76_76") (pintype "passive"))
      (node (ref "CON9") (pin "4") (pinfunction "D1+_4") (pintype "passive"))
      (node (ref "TVS5") (pin "2") (pinfunction "I/O2_2") (pintype "passive"))
    )
    (net (code "95") (name "/HDMI0_TX2_N") (class "Default")
      (node (ref "CON4") (pin "72") (pinfunction "72_72") (pintype "passive"))
      (node (ref "CON9") (pin "3") (pinfunction "D2-_3") (pintype "passive"))
      (node (ref "TVS5") (pin "9") (pinfunction "I/O8_9") (pintype "passive"))
    )
    (net (code "96") (name "/HDMI0_TX2_P") (class "Default")
      (node (ref "CON4") (pin "70") (pinfunction "70_70") (pintype "passive"))
      (node (ref "CON9") (pin "1") (pinfunction "D2+_1") (pintype "passive"))
      (node (ref "TVS5") (pin "1") (pinfunction "I/O1_1") (pintype "passive"))
    )
    (net (code "97") (name "/HDMI1_CEC") (class "Default")
      (node (ref "CON4") (pin "49") (pinfunction "49_49") (pintype "passive"))
    )
    (net (code "98") (name "/HDMI1_CLK_N") (class "Default")
      (node (ref "CON4") (pin "66") (pinfunction "66_66") (pintype "passive"))
    )
    (net (code "99") (name "/HDMI1_CLK_P") (class "Default")
      (node (ref "CON4") (pin "64") (pinfunction "64_64") (pintype "passive"))
    )
    (net (code "100") (name "/HDMI1_HOTPLUG") (class "Default")
      (node (ref "CON4") (pin "43") (pinfunction "43_43") (pintype "passive"))
    )
    (net (code "101") (name "/HDMI1_SCL") (class "Default")
      (node (ref "CON4") (pin "47") (pinfunction "47_47") (pintype "passive"))
    )
    (net (code "102") (name "/HDMI1_SDA") (class "Default")
      (node (ref "CON4") (pin "45") (pinfunction "45_45") (pintype "passive"))
    )
    (net (code "103") (name "/HDMI1_TX0_N") (class "Default")
      (node (ref "CON4") (pin "60") (pinfunction "60_60") (pintype "passive"))
    )
    (net (code "104") (name "/HDMI1_TX0_P") (class "Default")
      (node (ref "CON4") (pin "58") (pinfunction "58_58") (pintype "passive"))
    )
    (net (code "105") (name "/HDMI1_TX1_N") (class "Default")
      (node (ref "CON4") (pin "54") (pinfunction "54_54") (pintype "passive"))
    )
    (net (code "106") (name "/HDMI1_TX1_P") (class "Default")
      (node (ref "CON4") (pin "52") (pinfunction "52_52") (pintype "passive"))
    )
    (net (code "107") (name "/HDMI1_TX2_N") (class "Default")
      (node (ref "CON4") (pin "48") (pinfunction "48_48") (pintype "passive"))
    )
    (net (code "108") (name "/HDMI1_TX2_P") (class "Default")
      (node (ref "CON4") (pin "46") (pinfunction "46_46") (pintype "passive"))
    )
    (net (code "109") (name "/HDMI_PWR") (class "Default")
      (node (ref "C3") (pin "1") (pintype "passive"))
      (node (ref "CON9") (pin "18") (pinfunction "+5V_18") (pintype "passive"))
      (node (ref "IC4") (pin "6") (pinfunction "OUT_6") (pintype "passive"))
    )
    (net (code "110") (name "/ID_SC") (class "Default")
      (node (ref "CON3") (pin "35") (pinfunction "35_35") (pintype "passive"))
    )
    (net (code "111") (name "/ID_SD") (class "Default")
      (node (ref "CON3") (pin "36") (pinfunction "36_36") (pintype "passive"))
    )
    (net (code "112") (name "/OSCI") (class "Default")
      (node (ref "C4") (pin "1") (pintype "passive"))
      (node (ref "IC5") (pin "1") (pinfunction "OSCI_1") (pintype "passive"))
      (node (ref "XTAL1") (pin "1") (pinfunction "1_1") (pintype "passive"))
    )
    (net (code "113") (name "/OSCO") (class "Default")
      (node (ref "C5") (pin "1") (pintype "passive"))
      (node (ref "IC5") (pin "2") (pinfunction "OSCO_2") (pintype "passive"))
      (node (ref "XTAL1") (pin "2") (pinfunction "2_2") (pintype "passive"))
    )
    (net (code "114") (name "/PCIe_CLK_N") (class "Default")
      (node (ref "CON4") (pin "12") (pinfunction "12_12") (pintype "passive"))
    )
    (net (code "115") (name "/PCIe_CLK_P") (class "Default")
      (node (ref "CON4") (pin "10") (pinfunction "10_10") (pintype "passive"))
    )
    (net (code "116") (name "/PCIe_CLK_nREQ") (class "Default")
      (node (ref "CON4") (pin "2") (pinfunction "2_2") (pintype "passive"))
    )
    (net (code "117") (name "/PCIe_RX_N") (class "Default")
      (node (ref "CON4") (pin "18") (pinfunction "18_18") (pintype "passive"))
    )
    (net (code "118") (name "/PCIe_RX_P") (class "Default")
      (node (ref "CON4") (pin "16") (pinfunction "16_16") (pintype "passive"))
    )
    (net (code "119") (name "/PCIe_TX_N") (class "Default")
      (node (ref "CON4") (pin "24") (pinfunction "24_24") (pintype "passive"))
    )
    (net (code "120") (name "/PCIe_TX_P") (class "Default")
      (node (ref "CON4") (pin "22") (pinfunction "22_22") (pintype "passive"))
    )
    (net (code "121") (name "/PCIe_nRST") (class "Default")
      (node (ref "CON4") (pin "9") (pinfunction "9_9") (pintype "passive"))
    )
    (net (code "122") (name "/PI_LED_nPWR") (class "Default")
      (node (ref "CON3") (pin "95") (pinfunction "95_95") (pintype "passive"))
      (node (ref "IC13") (pin "2") (pinfunction "A_2") (pintype "input"))
    )
    (net (code "123") (name "/Pi_nLED_Activity") (class "Default")
      (node (ref "CON3") (pin "21") (pinfunction "21_21") (pintype "passive"))
      (node (ref "R48") (pin "1") (pinfunction "1_1") (pintype "passive"))
    )
    (net (code "124") (name "/RUN_PG") (class "Default")
      (node (ref "CON3") (pin "92") (pinfunction "92_92") (pintype "passive"))
      (node (ref "IC12") (pin "2") (pinfunction "A_2") (pintype "input"))
      (node (ref "J19") (pin "1") (pinfunction "1_1") (pintype "passive"))
      (node (ref "R44") (pin "1") (pinfunction "1_1") (pintype "passive"))
    )
    (net (code "125") (name "/Reserved_1") (class "Default")
      (node (ref "CON3") (pin "76") (pinfunction "76_76") (pintype "passive"))
    )
    (net (code "126") (name "/Reserved_2") (class "Default")
      (node (ref "CON4") (pin "4") (pinfunction "4_4") (pintype "passive"))
    )
    (net (code "127") (name "/Reserved_3") (class "Default")
      (node (ref "CON4") (pin "6") (pinfunction "6_6") (pintype "passive"))
    )
    (net (code "128") (name "/SCL0") (class "Default")
      (node (ref "CON3") (pin "80") (pinfunction "80_80") (pintype "passive"))
      (node (ref "IC5") (pin "6") (pinfunction "SCL_6") (pintype "passive"))
      (node (ref "J15") (pin "20") (pinfunction "20_20") (pintype "passive"))
    )
    (net (code "129") (name "/SDA0") (class "Default")
      (node (ref "CON3") (pin "82") (pinfunction "82_82") (pintype "passive"))
      (node (ref "IC5") (pin "5") (pinfunction "SDA_5") (pintype "passive"))
      (node (ref "J15") (pin "21") (pinfunction "21_21") (pintype "passive"))
    )
    (net (code "130") (name "/SD_CLK") (class "Default")
      (node (ref "CON3") (pin "57") (pinfunction "57_57") (pintype "passive"))
    )
    (net (code "131") (name "/SD_CMD") (class "Default")
      (node (ref "CON3") (pin "62") (pinfunction "62_62") (pintype "passive"))
    )
    (net (code "132") (name "/SD_DAT0") (class "Default")
      (node (ref "CON3") (pin "63") (pinfunction "63_63") (pintype "passive"))
    )
    (net (code "133") (name "/SD_DAT1") (class "Default")
      (node (ref "CON3") (pin "67") (pinfunction "67_67") (pintype "passive"))
    )
    (net (code "134") (name "/SD_DAT2") (class "Default")
      (node (ref "CON3") (pin "69") (pinfunction "69_69") (pintype "passive"))
    )
    (net (code "135") (name "/SD_DAT3") (class "Default")
      (node (ref "CON3") (pin "61") (pinfunction "61_61") (pintype "passive"))
    )
    (net (code "136") (name "/SD_DAT4") (class "Default")
      (node (ref "CON3") (pin "68") (pinfunction "68_68") (pintype "passive"))
    )
    (net (code "137") (name "/SD_DAT5") (class "Default")
      (node (ref "CON3") (pin "64") (pinfunction "64_64") (pintype "passive"))
    )
    (net (code "138") (name "/SD_DAT6") (class "Default")
      (node (ref "CON3") (pin "72") (pinfunction "72_72") (pintype "passive"))
    )
    (net (code "139") (name "/SD_DAT7") (class "Default")
      (node (ref "CON3") (pin "70") (pinfunction "70_70") (pintype "passive"))
    )
    (net (code "140") (name "/SD_PWR_ON") (class "Default")
      (node (ref "CON3") (pin "75") (pinfunction "75_75") (pintype "passive"))
    )
    (net (code "141") (name "/SD_VDD_Override") (class "Default")
      (node (ref "CON3") (pin "73") (pinfunction "73_73") (pintype "passive"))
    )
    (net (code "142") (name "/USB_N") (class "Default")
      (node (ref "CON4") (pin "3") (pinfunction "3_3") (pintype "passive"))
    )
    (net (code "143") (name "/USB_OTG_ID") (class "Default")
      (node (ref "CON4") (pin "1") (pinfunction "1_1") (pintype "passive"))
    )
    (net (code "144") (name "/USB_P") (class "Default")
      (node (ref "CON4") (pin "5") (pinfunction "5_5") (pintype "passive"))
    )
    (net (code "145") (name "/VDAC_COMP") (class "Default")
      (node (ref "CON4") (pin "11") (pinfunction "11_11") (pintype "passive"))
    )
    (net (code "146") (name "/WL_nDisable") (class "Default")
      (node (ref "CON3") (pin "89") (pinfunction "89_89") (pintype "passive"))
    )
    (net (code "147") (name "/nEXTRST") (class "Default")
      (node (ref "CON3") (pin "100") (pinfunction "100_100") (pintype "passive"))
    )
    (net (code "148") (name "/nRPIBOOT") (class "Default")
      (node (ref "CON3") (pin "93") (pinfunction "93_93") (pintype "passive"))
      (node (ref "J17") (pin "1") (pinfunction "1_1") (pintype "passive"))
    )
    (net (code "149") (name "/nRTC_INT") (class "Default")
      (node (ref "C1") (pin "1") (pintype "passive"))
      (node (ref "IC5") (pin "3") (pinfunction "INT_3") (pintype "passive"))
      (node (ref "R14") (pin "1") (pinfunction "1_1") (pintype "passive"))
    )
    (net (code "152") (name "CHASSIS") (class "Default")
      (node (ref "CON5") (pin "Shell") (pinfunction "Shield_Shell") (pintype "passive"))
      (node (ref "CON9") (pin "20") (pinfunction "SHIELD_20") (pintype "passive"))
      (node (ref "SW1") (pin "3") (pinfunction "3_3") (pintype "passive"))
      (node (ref "SW2") (pin "3") (pinfunction "3_3") (pintype "passive"))
    )
    (net (code "153") (name "GND") (class "Default")
      (node (ref "BAT1") (pin "2") (pinfunction "2_2") (pintype "passive"))
      (node (ref "C2") (pin "2") (pintype "passive"))
      (node (ref "C25") (pin "2") (pintype "passive"))
      (node (ref "C29") (pin "1") (pintype "passive"))
      (node (ref "C3") (pin "2") (pintype "passive"))
      (node (ref "C4") (pin "2") (pintype "passive"))
      (node (ref "C43") (pin "2") (pintype "passive"))
      (node (ref "C5") (pin "2") (pintype "passive"))
      (node (ref "CON3") (pin "1") (pinfunction "1_1") (pintype "passive"))
      (node (ref "CON3") (pin "13") (pinfunction "13_13") (pintype "passive"))
      (node (ref "CON3") (pin "14") (pinfunction "14_14") (pintype "passive"))
      (node (ref "CON3") (pin "2") (pinfunction "2_2") (pintype "passive"))
      (node (ref "CON3") (pin "22") (pinfunction "22_22") (pintype "passive"))
      (node (ref "CON3") (pin "23") (pinfunction "23_23") (pintype "passive"))
      (node (ref "CON3") (pin "32") (pinfunction "32_32") (pintype "passive"))
      (node (ref "CON3") (pin "33") (pinfunction "33_33") (pintype "passive"))
      (node (ref "CON3") (pin "42") (pinfunction "42_42") (pintype "passive"))
      (node (ref "CON3") (pin "43") (pinfunction "43_43") (pintype "passive"))
      (node (ref "CON3") (pin "52") (pinfunction "52_52") (pintype "passive"))
      (node (ref "CON3") (pin "53") (pinfunction "53_53") (pintype "passive"))
      (node (ref "CON3") (pin "59") (pinfunction "59_59") (pintype "passive"))
      (node (ref "CON3") (pin "60") (pinfunction "60_60") (pintype "passive"))
      (node (ref "CON3") (pin "65") (pinfunction "65_65") (pintype "passive"))
      (node (ref "CON3") (pin "66") (pinfunction "66_66") (pintype "passive"))
      (node (ref "CON3") (pin "7") (pinfunction "7_7") (pintype "passive"))
      (node (ref "CON3") (pin "71") (pinfunction "71_71") (pintype "passive"))
      (node (ref "CON3") (pin "74") (pinfunction "74_74") (pintype "passive"))
      (node (ref "CON3") (pin "8") (pinfunction "8_8") (pintype "passive"))
      (node (ref "CON3") (pin "98") (pinfunction "98_98") (pintype "passive"))
      (node (ref "CON4") (pin "13") (pinfunction "13_13") (pintype "passive"))
      (node (ref "CON4") (pin "14") (pinfunction "14_14") (pintype "passive"))
      (node (ref "CON4") (pin "19") (pinfunction "19_19") (pintype "passive"))
      (node (ref "CON4") (pin "20") (pinfunction "20_20") (pintype "passive"))
      (node (ref "CON4") (pin "25") (pinfunction "25_25") (pintype "passive"))
      (node (ref "CON4") (pin "26") (pinfunction "26_26") (pintype "passive"))
      (node (ref "CON4") (pin "31") (pinfunction "31_31") (pintype "passive"))
      (node (ref "CON4") (pin "32") (pinfunction "32_32") (pintype "passive"))
      (node (ref "CON4") (pin "37") (pinfunction "37_37") (pintype "passive"))
      (node (ref "CON4") (pin "38") (pinfunction "38_38") (pintype "passive"))
      (node (ref "CON4") (pin "44") (pinfunction "44_44") (pintype "passive"))
      (node (ref "CON4") (pin "50") (pinfunction "50_50") (pintype "passive"))
      (node (ref "CON4") (pin "55") (pinfunction "55_55") (pintype "passive"))
      (node (ref "CON4") (pin "56") (pinfunction "56_56") (pintype "passive"))
      (node (ref "CON4") (pin "61") (pinfunction "61_61") (pintype "passive"))
      (node (ref "CON4") (pin "62") (pinfunction "62_62") (pintype "passive"))
      (node (ref "CON4") (pin "67") (pinfunction "67_67") (pintype "passive"))
      (node (ref "CON4") (pin "68") (pinfunction "68_68") (pintype "passive"))
      (node (ref "CON4") (pin "7") (pinfunction "7_7") (pintype "passive"))
      (node (ref "CON4") (pin "73") (pinfunction "73_73") (pintype "passive"))
      (node (ref "CON4") (pin "74") (pinfunction "74_74") (pintype "passive"))
      (node (ref "CON4") (pin "79") (pinfunction "79_79") (pintype "passive"))
      (node (ref "CON4") (pin "8") (pinfunction "8_8") (pintype "passive"))
      (node (ref "CON4") (pin "80") (pinfunction "80_80") (pintype "passive"))
      (node (ref "CON4") (pin "85") (pinfunction "85_85") (pintype "passive"))
      (node (ref "CON4") (pin "86") (pinfunction "86_86") (pintype "passive"))
      (node (ref "CON4") (pin "91") (pinfunction "91_91") (pintype "passive"))
      (node (ref "CON4") (pin "92") (pinfunction "92_92") (pintype "passive"))
      (node (ref "CON4") (pin "97") (pinfunction "97_97") (pintype "passive"))
      (node (ref "CON4") (pin "98") (pinfunction "98_98") (pintype "passive"))
      (node (ref "CON9") (pin "11") (pinfunction "CKS_11") (pintype "passive"))
      (node (ref "CON9") (pin "17") (pinfunction "GND_17") (pintype "passive"))
      (node (ref "CON9") (pin "2") (pinfunction "D2S_2") (pintype "passive"))
      (node (ref "CON9") (pin "5") (pinfunction "D1S_5") (pintype "passive"))
      (node (ref "CON9") (pin "8") (pinfunction "D0S_8") (pintype "passive"))
      (node (ref "IC12") (pin "3") (pinfunction "GND_3") (pintype "power_in"))
      (node (ref "IC13") (pin "3") (pinfunction "GND_3") (pintype "power_in"))
      (node (ref "IC3") (pin "3") (pinfunction "GND_3") (pintype "power_in"))
      (node (ref "IC4") (pin "2") (pinfunction "GND_2") (pintype "passive"))
      (node (ref "IC5") (pin "4") (pinfunction "GND_4") (pintype "passive"))
      (node (ref "J15") (pin "1") (pinfunction "1_1") (pintype "passive"))
      (node (ref "J15") (pin "10") (pinfunction "10_10") (pintype "passive"))
      (node (ref "J15") (pin "13") (pinfunction "13_13") (pintype "passive"))
      (node (ref "J15") (pin "16") (pinfunction "16_16") (pintype "passive"))
      (node (ref "J15") (pin "19") (pinfunction "19_19") (pintype "passive"))
      (node (ref "J15") (pin "4") (pinfunction "4_4") (pintype "passive"))
      (node (ref "J15") (pin "7") (pinfunction "7_7") (pintype "passive"))
      (node (ref "J15") (pin "MP1") (pinfunction "MP1_MP1") (pintype "passive"))
      (node (ref "J15") (pin "MP2") (pinfunction "MP2_MP2") (pintype "passive"))
      (node (ref "J15") (pin "MP3") (pinfunction "MP3_MP3") (pintype "passive"))
      (node (ref "J15") (pin "MP4") (pinfunction "MP4_MP4") (pintype "passive"))
      (node (ref "J16") (pin "2") (pinfunction "2_2") (pintype "passive"))
      (node (ref "J17") (pin "2") (pinfunction "2_2") (pintype "passive"))
      (node (ref "J18") (pin "2") (pinfunction "2_2") (pintype "passive"))
      (node (ref "J19") (pin "2") (pinfunction "2_2") (pintype "passive"))
      (node (ref "J3") (pin "8") (pinfunction "8_8") (pintype "passive"))
      (node (ref "J4") (pin "6") (pinfunction "6_6") (pintype "passive"))
      (node (ref "J6") (pin "3") (pinfunction "3_3") (pintype "passive"))
      (node (ref "J6") (pin "4") (pinfunction "4_4") (pintype "passive"))
      (node (ref "R17") (pin "1") (pinfunction "1_1") (pintype "passive"))
      (node (ref "R38") (pin "2") (pinfunction "2_2") (pintype "passive"))
      (node (ref "R39") (pin "2") (pinfunction "2_2") (pintype "passive"))
      (node (ref "R46") (pin "2") (pinfunction "2_2") (pintype "passive"))
      (node (ref "TP5") (pin "1") (pinfunction "1_1") (pintype "passive"))
      (node (ref "TR3") (pin "2") (pinfunction "E_2") (pintype "passive"))
      (node (ref "TVS12") (pin "3") (pinfunction "GND_3") (pintype "passive"))
      (node (ref "TVS5") (pin "3") (pinfunction "GND_3") (pintype "passive"))
      (node (ref "VR1") (pin "1") (pinfunction "GND_1") (pintype "passive"))
    )
    (net (code "154") (name "Net-(C43-Pad1)") (class "Default")
      (node (ref "C43") (pin "1") (pintype "passive"))
      (node (ref "CON5") (pin "5") (pinfunction "VCC/GND_5") (pintype "passive"))
      (node (ref "CON5") (pin "6") (pinfunction "VCC/GND_6") (pintype "passive"))
    )
    (net (code "155") (name "Net-(CON5-Pad12)") (class "Default")
      (node (ref "CON5") (pin "12") (pinfunction "12_12") (pintype "passive"))
      (node (ref "R38") (pin "1") (pinfunction "1_1") (pintype "passive"))
    )
    (net (code "156") (name "Net-(CON5-Pad13)") (class "Default")
      (node (ref "CON5") (pin "13") (pinfunction "13_13") (pintype "passive"))
      (node (ref "R39") (pin "1") (pinfunction "1_1") (pintype "passive"))
    )
    (net (code "157") (name "Net-(D1-A)") (class "Default")
      (node (ref "BAT1") (pin "1") (pinfunction "1_1") (pintype "passive"))
      (node (ref "D1") (pin "1") (pinfunction "A_1") (pintype "passive"))
    )
    (net (code "158") (name "Net-(IC3-A)") (class "Default")
      (node (ref "C1") (pin "2") (pintype "passive"))
      (node (ref "IC3") (pin "2") (pinfunction "A_2") (pintype "input"))
      (node (ref "R15") (pin "1") (pinfunction "1_1") (pintype "passive"))
    )
    (net (code "159") (name "Net-(IC3-Y)") (class "Default")
      (node (ref "IC3") (pin "4") (pinfunction "Y_4") (pintype "output"))
      (node (ref "R78") (pin "1") (pinfunction "1_1") (pintype "passive"))
    )
    (net (code "160") (name "Net-(IC4-EN)") (class "Default")
      (node (ref "IC4") (pin "3") (pinfunction "EN_3") (pintype "passive"))
      (node (ref "R16") (pin "1") (pinfunction "1_1") (pintype "passive"))
    )
    (net (code "161") (name "Net-(IC4-ILIM)") (class "Default")
      (node (ref "IC4") (pin "5") (pinfunction "ILIM_5") (pintype "passive"))
      (node (ref "R17") (pin "2") (pinfunction "2_2") (pintype "passive"))
    )
    (net (code "162") (name "Net-(IC5-VDD)") (class "Default")
      (node (ref "D1") (pin "3") (pinfunction "K_3") (pintype "passive"))
      (node (ref "IC5") (pin "8") (pinfunction "VDD_8") (pintype "passive"))
    )
    (net (code "163") (name "Net-(IC12-Y)") (class "Default")
      (node (ref "IC12") (pin "4") (pinfunction "Y_4") (pintype "output"))
      (node (ref "SW1") (pin "1") (pinfunction "1_1") (pintype "passive"))
    )
    (net (code "164") (name "Net-(IC13-Y)") (class "Default")
      (node (ref "IC13") (pin "4") (pinfunction "Y_4") (pintype "output"))
      (node (ref "R47") (pin "2") (pinfunction "2_2") (pintype "passive"))
    )
    (net (code "165") (name "Net-(LED1-Pad2)") (class "Default")
      (node (ref "LED1") (pin "2") (pinfunction "2_2") (pintype "passive"))
      (node (ref "R47") (pin "1") (pinfunction "1_1") (pintype "passive"))
    )
    (net (code "166") (name "Net-(LED2-Pad2)") (class "Default")
      (node (ref "LED2") (pin "2") (pinfunction "2_2") (pintype "passive"))
      (node (ref "R48") (pin "2") (pinfunction "2_2") (pintype "passive"))
    )
    (net (code "167") (name "Net-(R45-Pad2)") (class "Default")
      (node (ref "R45") (pin "2") (pinfunction "2_2") (pintype "passive"))
      (node (ref "SW2") (pin "2") (pinfunction "2_2") (pintype "passive"))
    )
    (net (code "168") (name "Net-(TR3-B)") (class "Default")
      (node (ref "R45") (pin "1") (pinfunction "1_1") (pintype "passive"))
      (node (ref "R46") (pin "1") (pinfunction "1_1") (pintype "passive"))
      (node (ref "TR3") (pin "1") (pinfunction "B_1") (pintype "passive"))
    )
    (net (code "169") (name "Net-(TR3-C)") (class "Default")
      (node (ref "R44") (pin "2") (pinfunction "2_2") (pintype "passive"))
      (node (ref "TR3") (pin "3") (pinfunction "C_3") (pintype "passive"))
    )
    (net (code "170") (name "unconnected-(CON9-UTILITY{slash}HEAC+-Pad14)") (class "Default")
      (node (ref "CON9") (pin "14") (pinfunction "UTILITY/HEAC+_14") (pintype "passive+no_connect"))
    )
    (net (code "171") (name "unconnected-(IC3-NC-Pad1)") (class "Default")
      (node (ref "IC3") (pin "1") (pinfunction "NC_1") (pintype "input+no_connect"))
    )
    (net (code "172") (name "unconnected-(IC4-FAULT-Pad4)") (class "Default")
      (node (ref "IC4") (pin "4") (pinfunction "FAULT_4") (pintype "passive"))
    )
    (net (code "173") (name "unconnected-(IC5-CLKOUT-Pad7)") (class "Default")
      (node (ref "IC5") (pin "7") (pinfunction "CLKOUT_7") (pintype "passive"))
    )
    (net (code "174") (name "unconnected-(IC12-NC-Pad1)") (class "Default")
      (node (ref "IC12") (pin "1") (pinfunction "NC_1") (pintype "input+no_connect"))
    )
    (net (code "175") (name "unconnected-(IC13-NC-Pad1)") (class "Default")
      (node (ref "IC13") (pin "1") (pinfunction "NC_1") (pintype "input+no_connect"))
    )
    (net (code "176") (name "unconnected-(J15-Pad17)") (class "Default")
      (node (ref "J15") (pin "17") (pinfunction "17_17") (pintype "passive+no_connect"))
    )
    (net (code "177") (name "unconnected-(J15-Pad18)") (class "Default")
      (node (ref "J15") (pin "18") (pinfunction "18_18") (pintype "passive+no_connect"))
    )
  )
)
